# WX0_012_462DL.net
KiCad netlist of a schematic drawn in Altium Designer
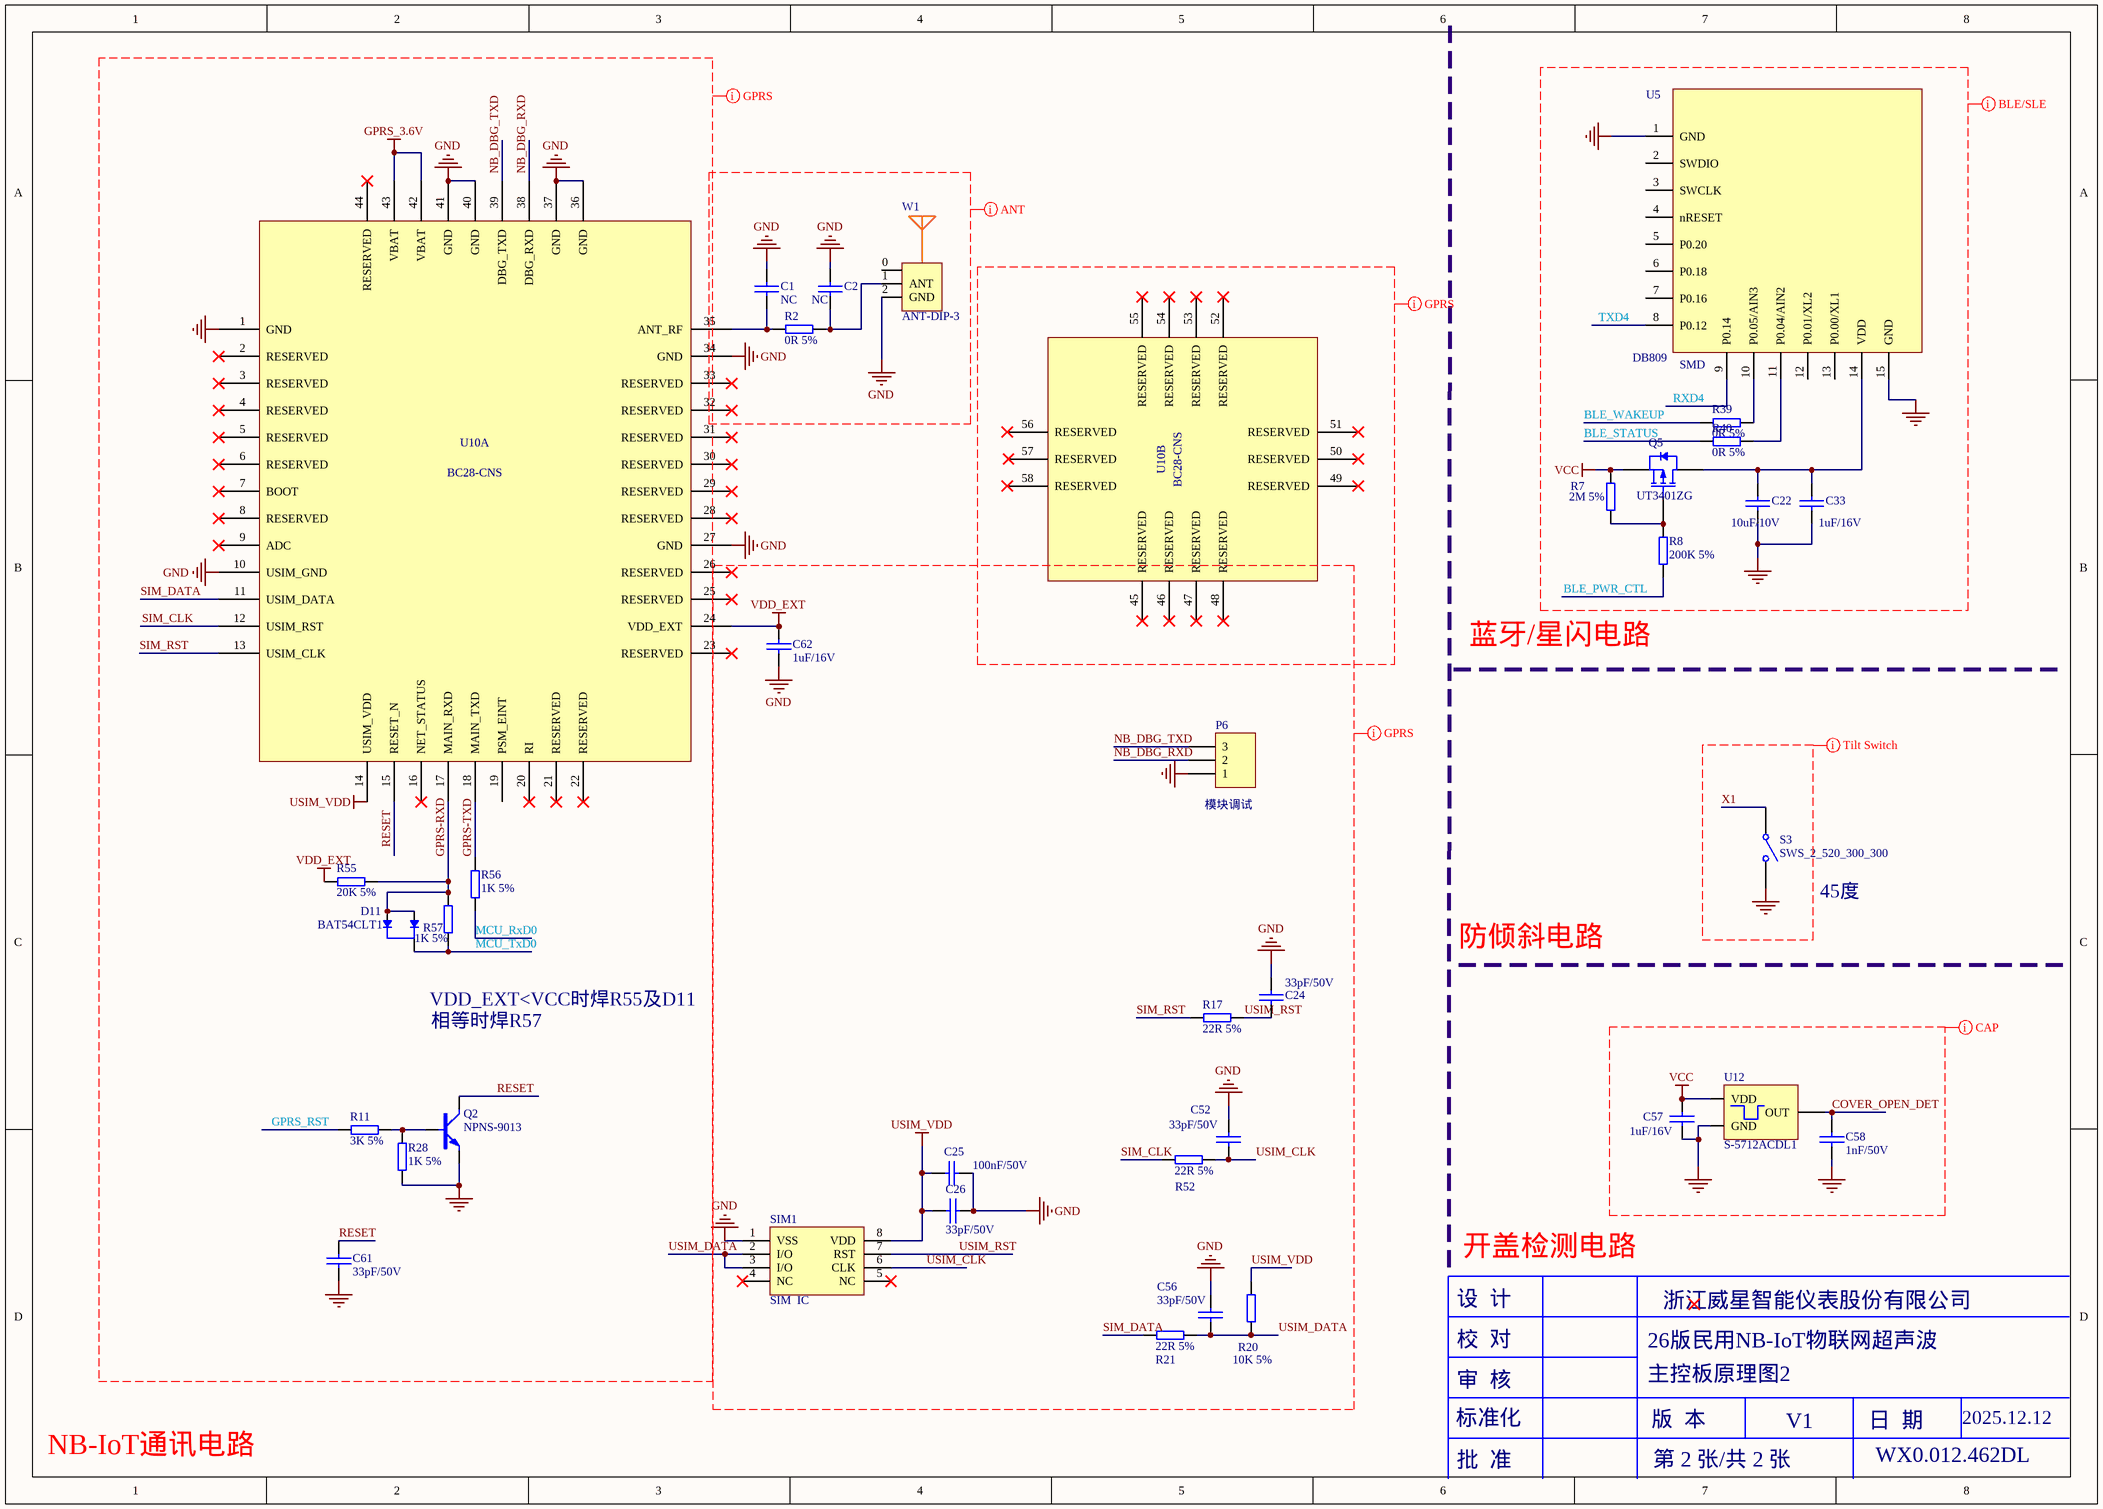
[diagram p0: WX0.012.462DL.SchDoc]

(export (version "E")
  (design (tool "Eeschema 10.0.6"))
  (components
    (comp (ref "C1")
      (value "NC")
      (footprint "CAP0402")
      (libsource (lib "Database_Libs2") (part "CC03JPO9_12P"))
    )
    (comp (ref "C2")
      (value "NC")
      (footprint "CAP0402")
      (libsource (lib "Database_Libs2") (part "CC03JPO9_12P"))
    )
    (comp (ref "C22")
      (value "10uF/10V")
      (footprint "CAP0402")
      (description "106pF,10 V,±10%,0603,村田,GRM188R61A106KE47D")
      (fields (field (name "PART NUMBER") "101020103-0026"))
      (libsource (lib "Database_Libs2") (part "CC03K5R6_10U"))
    )
    (comp (ref "C24")
      (value "33pF/50V")
      (footprint "CAP0402")
      (description "33pF,50 V,±10%,0603,国巨,CC0603KRNPO9BN33")
      (fields (field (name "PART NUMBER") "101020103-0027"))
      (libsource (lib "Database_Libs2") (part "CC03KPO9_33P"))
    )
    (comp (ref "C25")
      (value "100nF/50V")
      (footprint "CAP0402")
      (description "104pF,50 V,±10%,0603,国巨,CC0603KRX7R9BB104")
      (fields (field (name "PART NUMBER") "101020103-0021"))
      (libsource (lib "Database_Libs2") (part "CC03K7R9_100N"))
    )
    (comp (ref "C26")
      (value "33pF/50V")
      (footprint "CAP0402")
      (description "33pF,50 V,±10%,0603,国巨,CC0603KRNPO9BN33")
      (fields (field (name "PART NUMBER") "101020103-0027"))
      (libsource (lib "Database_Libs2") (part "CC03KPO9_33P"))
    )
    (comp (ref "C33")
      (value "1uF/16V")
      (footprint "CAP0402")
      (description "105pF,16 V,±10%,0603,国巨,CC0603KRX7R7BB105")
      (fields (field (name "PART NUMBER") "101020103-0003"))
      (libsource (lib "Database_Libs2") (part "CC03K7R7_1U"))
    )
    (comp (ref "C52")
      (value "33pF/50V")
      (footprint "CAP0402")
      (description "33pF,50 V,±10%,0603,国巨,CC0603KRNPO9BN33")
      (fields (field (name "PART NUMBER") "101020103-0027"))
      (libsource (lib "Database_Libs2") (part "CC03KPO9_33P"))
    )
    (comp (ref "C56")
      (value "33pF/50V")
      (footprint "CAP0402")
      (description "33pF,50 V,±10%,0603,国巨,CC0603KRNPO9BN33")
      (fields (field (name "PART NUMBER") "101020103-0027"))
      (libsource (lib "Database_Libs2") (part "CC03KPO9_33P"))
    )
    (comp (ref "C57")
      (value "1uF/16V")
      (footprint "CAP0402")
      (description "105pF,16 V,±10%,0603,国巨,CC0603KRX7R7BB105")
      (fields (field (name "PART NUMBER") "101020103-0003"))
      (libsource (lib "Database_Libs2") (part "CC03K7R7_1U"))
    )
    (comp (ref "C58")
      (value "1nF/50V")
      (footprint "CAP0402")
      (description "102pF,50 V,±10%,0603,国巨,CC0603KRX7R9BB102")
      (fields (field (name "PART NUMBER") "101020103-0022"))
      (libsource (lib "Database_Libs2") (part "CC03K7R9_1N"))
    )
    (comp (ref "C61")
      (value "33pF/50V")
      (footprint "CAP0402")
      (description "33pF,50 V,±10%,0603,国巨,CC0603KRNPO9BN33")
      (fields (field (name "PART NUMBER") "101020103-0027"))
      (libsource (lib "Database_Libs2") (part "CC03KPO9_33P"))
    )
    (comp (ref "C62")
      (value "1uF/16V")
      (footprint "CAP0402")
      (description "105pF,16 V,±10%,0603,国巨,CC0603KRX7R7BB105")
      (fields (field (name "PART NUMBER") "101020103-0003"))
      (libsource (lib "Database_Libs1") (part "CC03K7R7_1U"))
    )
    (comp (ref "D11")
      (value "BAT54CLT1")
      (footprint "SOT-23")
      (description "BAT54CLT1，SOT23-3,SOT23-3,0.2 A,0.8 V,30 V,安森美,BAT54CLT1")
      (fields (field (name "PART NUMBER") "101040101-0038"))
      (libsource (lib "Database_Libs2") (part "02_BAT54CLT1"))
    )
    (comp (ref "P6")
      (value "模块调试")
      (footprint "PIN254_1*3*WXHJ")
      (description "1*3 ，Φ1.0 ，2.54mm，直脚,无需焊接器件")
      (fields (field (name "PART NUMBER") "AD_WXHJ_PinHeader_04"))
      (libsource (lib "Database_Libs2") (part "PIN254_1*3*WXHJ"))
    )
    (comp (ref "Q2")
      (value "NPNS-9013")
      (footprint "SOT-323-3_L2.0-W1.3-P1.30-LS2.1-BR")
      (description "9013,NPN,SOT-23,长电,S9013")
      (fields (field (name "PART NUMBER") "101040201-0002"))
      (libsource (lib "Database_Libs2") (part "03_NPNS-9013"))
    )
    (comp (ref "Q5")
      (value "UT3401ZG")
      (footprint "SOT-23")
      (description "UT3401ZG,P-MOS,SOT-23,UTC,UT3401ZG")
      (fields (field (name "PART NUMBER") "101040201-0013"))
      (libsource (lib "Database_Libs2") (part "03_P-UT3401ZG"))
    )
    (comp (ref "R2")
      (value "0R 5%")
      (footprint "RES0402")
      (description "国巨,±5%,0603,,155 ℃,-55 ℃,RC0603J2-070RL,无铅,200 ppm/℃,1/10W,,0R")
      (fields (field (name "PART NUMBER") "101010103-0001"))
      (libsource (lib "Database_Libs2") (part "RC03J_0R"))
    )
    (comp (ref "R7")
      (value "2M 5%")
      (footprint "RES0402")
      (description "国巨,±5%,0603,,155 ℃,-55 ℃,RC0603JR-072ML,含铅,100 ppm/℃,1/10W,,2M")
      (fields (field (name "PART NUMBER") "101010103-0025"))
      (libsource (lib "Database_Libs2") (part "RC03J_2M"))
    )
    (comp (ref "R8")
      (value "200K 5%")
      (footprint "RES0402")
      (description "10K±5%,1/10W,0603")
      (fields (field (name "PART NUMBER") "101010103-0003"))
      (libsource (lib "Database_Libs1") (part "RC03JF_10K"))
    )
    (comp (ref "R11")
      (value "3K 5%")
      (footprint "RES0402")
      (description "国巨,±5%,0603,,155 ℃,-55 ℃,RC0603JR-073KL,无铅,100 ppm/℃,1/10W,,3K")
      (fields (field (name "PART NUMBER") "101010103-0006"))
      (libsource (lib "Database_Libs2") (part "RC03J_3K"))
    )
    (comp (ref "R17")
      (value "22R 5%")
      (footprint "RES0402")
      (description "国巨,±5%,0603,,155 ℃,-55 ℃,RC0603JR-0722RL,无铅,200 ppm/℃,1/10W,,22欧")
      (fields (field (name "PART NUMBER") "101010103-0009"))
      (libsource (lib "Database_Libs2") (part "RC03J_22R"))
    )
    (comp (ref "R20")
      (value "10K 5%")
      (footprint "RES0402")
      (description "国巨,±5%,0603,,155 ℃,-55 ℃,RC0603JR-0710KL,无铅,200 ppm/℃,1/10W,,10K")
      (fields (field (name "PART NUMBER") "101010103-0003"))
      (libsource (lib "Database_Libs2") (part "RC03J_10K"))
    )
    (comp (ref "R21")
      (value "22R 5%")
      (footprint "RES0402")
      (description "国巨,±5%,0603,,155 ℃,-55 ℃,RC0603JR-0722RL,无铅,200 ppm/℃,1/10W,,22欧")
      (fields (field (name "PART NUMBER") "101010103-0009"))
      (libsource (lib "Database_Libs2") (part "RC03J_22R"))
    )
    (comp (ref "R28")
      (value "1K 5%")
      (footprint "RES0402")
      (description "1K,±5%,1/10W,0603,国巨,RC0603JR-071KL")
      (fields (field (name "PART NUMBER") "101010103-0008"))
      (libsource (lib "Database_Libs2") (part "RC03J_1K"))
    )
    (comp (ref "R39")
      (value "0R 5%")
      (footprint "RES0402")
      (description "国巨,±5%,0603,,155 ℃,-55 ℃,RC0603J2-070RL,无铅,200 ppm/℃,1/10W,,0R")
      (fields (field (name "PART NUMBER") "101010103-0001"))
      (libsource (lib "Database_Libs2") (part "RC03J_0R"))
    )
    (comp (ref "R40")
      (value "0R 5%")
      (footprint "RES0402")
      (description "国巨,±5%,0603,,155 ℃,-55 ℃,RC0603J2-070RL,无铅,200 ppm/℃,1/10W,,0R")
      (fields (field (name "PART NUMBER") "101010103-0001"))
      (libsource (lib "Database_Libs2") (part "RC03J_0R"))
    )
    (comp (ref "R52")
      (value "22R 5%")
      (footprint "RES0402")
      (description "国巨,±5%,0603,,155 ℃,-55 ℃,RC0603JR-0722RL,无铅,200 ppm/℃,1/10W,,22欧")
      (fields (field (name "PART NUMBER") "101010103-0009"))
      (libsource (lib "Database_Libs2") (part "RC03J_22R"))
    )
    (comp (ref "R55")
      (value "20K 5%")
      (footprint "RES0402")
      (description "国巨,±5%,0603,,155 ℃,-55 ℃,RC0603JR-0720KL,无铅,200 ppm/℃,1/10W,,20K")
      (fields (field (name "PART NUMBER") "101010103-0004"))
      (libsource (lib "Database_Libs2") (part "RC03J_20K"))
    )
    (comp (ref "R56")
      (value "1K 5%")
      (footprint "RES0402")
      (description "220K,±5%,1/10W,0603,国巨,RC0603JR-07220KL")
      (fields (field (name "PART NUMBER") "101010103-0044"))
      (libsource (lib "Database_Libs2") (part "RC03J_220K"))
    )
    (comp (ref "R57")
      (value "1K 5%")
      (footprint "RES0402")
      (description "220K,±5%,1/10W,0603,国巨,RC0603JR-07220KL")
      (fields (field (name "PART NUMBER") "101010103-0044"))
      (libsource (lib "Database_Libs2") (part "RC03J_220K"))
    )
    (comp (ref "S3")
      (value "SWS_2_520_300_300")
      (footprint "SWS_2_520_300")
      (description "CSX-SEN-645B,垂直45°开关转换,3*5.2mm,360°任意方位倾斜检测,深圳市成晟科技有限公司")
      (fields (field (name "PART NUMBER") "1011001-0051"))
      (libsource (lib "Database_Libs2") (part "07_SWS_2_520_300_300"))
    )
    (comp (ref "SIM1")
      (value "SIM  IC")
      (footprint "SIMIC")
      (libsource (lib "PCB_Project") (part "SIMCARD_1"))
    )
    (comp (ref "U5")
      (value "DB809")
      (footprint "DB809")
      (description "北高智蓝牙模块DB809")
      (fields (field (name "PART NUMBER") "1011402-0194") (field (name "SMD/DIP") "SMD"))
      (libsource (lib "Database_Libs2") (part "01_DB809"))
    )
    (comp (ref "U10")
      (value "BC28-CNS")
      (footprint "BC28-CNS")
      (description "BC28-CNS Moudle 58Pin 15.8X17.7mm H2.2mm RO")
      (fields (field (name "MANUFACTURER") "Quectel"))
      (libsource (lib "") (part "BC28-CNS_1"))
    )
    (comp (ref "U12")
      (value "S-5712ACDL1")
      (footprint "SOT-23")
      (description "S-5712ACDL1,SOT23-3,3.5 V,1.6 V,2 uA,精工电子,S-5712ACDL1")
      (fields (field (name "PART NUMBER") "1010504-0002"))
      (libsource (lib "Database_Libs2") (part "01_S-5712ACDL1"))
    )
    (comp (ref "W1")
      (value "ANT-DIP-3")
      (footprint "ANT-DIP-3")
      (libsource (lib "Connect_WX") (part "ANT-DIP-3"))
    )
  )
  (nets
    (net (code "1") (name "/BLE_PWR_CTL") (class "Default")
      (node (ref "R8") (pin "1") (pinfunction "1_1") (pintype "passive"))
    )
    (net (code "2") (name "/BLE_STATUS") (class "Default")
      (node (ref "R40") (pin "2") (pinfunction "2_2") (pintype "passive"))
    )
    (net (code "3") (name "/BLE_WAKEUP") (class "Default")
      (node (ref "R39") (pin "1") (pinfunction "1_1") (pintype "passive"))
    )
    (net (code "4") (name "/COVER_OPEN_DET") (class "Default")
      (node (ref "C58") (pin "1") (pinfunction "1_1") (pintype "passive"))
      (node (ref "U12") (pin "2") (pinfunction "OUT_2") (pintype "passive"))
    )
    (net (code "5") (name "/GPRS-RXD") (class "Default")
      (node (ref "D11") (pin "1") (pinfunction "A_1") (pintype "passive"))
      (node (ref "D11") (pin "2") (pinfunction "A_2") (pintype "passive"))
      (node (ref "R55") (pin "2") (pinfunction "2_2") (pintype "passive"))
      (node (ref "R57") (pin "1") (pinfunction "1_1") (pintype "passive"))
      (node (ref "U10") (pin "17") (pinfunction "MAIN_RXD_17") (pintype "passive"))
    )
    (net (code "6") (name "/GPRS-TXD") (class "Default")
      (node (ref "R56") (pin "2") (pinfunction "2_2") (pintype "passive"))
      (node (ref "U10") (pin "18") (pinfunction "MAIN_TXD_18") (pintype "passive"))
    )
    (net (code "7") (name "/GPRS_RST") (class "Default")
      (node (ref "R11") (pin "1") (pinfunction "1_1") (pintype "passive"))
    )
    (net (code "8") (name "/MCU_RxD0") (class "Default")
      (node (ref "R56") (pin "1") (pinfunction "1_1") (pintype "passive"))
    )
    (net (code "9") (name "/MCU_TxD0") (class "Default")
      (node (ref "D11") (pin "3") (pinfunction "C_3") (pintype "passive"))
      (node (ref "R57") (pin "2") (pinfunction "2_2") (pintype "passive"))
    )
    (net (code "10") (name "/NB_DBG_RXD") (class "Default")
      (node (ref "P6") (pin "2") (pinfunction "2_2") (pintype "passive"))
      (node (ref "U10") (pin "38") (pinfunction "DBG_RXD_38") (pintype "passive"))
    )
    (net (code "11") (name "/NB_DBG_TXD") (class "Default")
      (node (ref "P6") (pin "3") (pinfunction "3_3") (pintype "passive"))
      (node (ref "U10") (pin "39") (pinfunction "DBG_TXD_39") (pintype "passive"))
    )
    (net (code "12") (name "/RESET") (class "Default")
      (node (ref "C61") (pin "1") (pinfunction "1_1") (pintype "passive"))
      (node (ref "Q2") (pin "3") (pinfunction "C_3") (pintype "passive"))
      (node (ref "U10") (pin "15") (pinfunction "RESET_N_15") (pintype "passive"))
    )
    (net (code "13") (name "/RXD4") (class "Default")
      (node (ref "U5") (pin "9") (pinfunction "P0.14_9") (pintype "passive"))
    )
    (net (code "14") (name "/SIM_CLK") (class "Default")
      (node (ref "R52") (pin "1") (pinfunction "1_1") (pintype "passive"))
      (node (ref "U10") (pin "12") (pinfunction "USIM_RST_12") (pintype "passive"))
    )
    (net (code "15") (name "/SIM_DATA") (class "Default")
      (node (ref "R21") (pin "1") (pinfunction "1_1") (pintype "passive"))
      (node (ref "U10") (pin "11") (pinfunction "USIM_DATA_11") (pintype "passive"))
    )
    (net (code "16") (name "/SIM_RST") (class "Default")
      (node (ref "R17") (pin "1") (pinfunction "1_1") (pintype "passive"))
      (node (ref "U10") (pin "13") (pinfunction "USIM_CLK_13") (pintype "passive"))
    )
    (net (code "17") (name "/TXD4") (class "Default")
      (node (ref "U5") (pin "8") (pinfunction "P0.12_8") (pintype "passive"))
    )
    (net (code "18") (name "/USIM_CLK") (class "Default")
      (node (ref "C52") (pin "1") (pinfunction "1_1") (pintype "passive"))
      (node (ref "R52") (pin "2") (pinfunction "2_2") (pintype "passive"))
      (node (ref "SIM1") (pin "6") (pinfunction "CLK_6") (pintype "passive"))
    )
    (net (code "19") (name "/USIM_DATA") (class "Default")
      (node (ref "C56") (pin "1") (pinfunction "1_1") (pintype "passive"))
      (node (ref "R20") (pin "1") (pinfunction "1_1") (pintype "passive"))
      (node (ref "R21") (pin "2") (pinfunction "2_2") (pintype "passive"))
      (node (ref "SIM1") (pin "2") (pinfunction "I/O_2") (pintype "passive"))
      (node (ref "SIM1") (pin "3") (pinfunction "I/O_3") (pintype "passive"))
    )
    (net (code "20") (name "/USIM_RST") (class "Default")
      (node (ref "C24") (pin "1") (pinfunction "1_1") (pintype "passive"))
      (node (ref "R17") (pin "2") (pinfunction "2_2") (pintype "passive"))
      (node (ref "SIM1") (pin "7") (pinfunction "RST_7") (pintype "passive"))
    )
    (net (code "21") (name "/X1") (class "Default") (node (ref "S3") (pin "1") (pintype "passive")))
    (net (code "22") (name "GND") (class "Default")
      (node (ref "C1") (pin "2") (pinfunction "2_2") (pintype "passive"))
      (node (ref "C2") (pin "2") (pinfunction "2_2") (pintype "passive"))
      (node (ref "C22") (pin "2") (pinfunction "2_2") (pintype "passive"))
      (node (ref "C24") (pin "2") (pinfunction "2_2") (pintype "passive"))
      (node (ref "C25") (pin "1") (pinfunction "1_1") (pintype "passive"))
      (node (ref "C26") (pin "2") (pinfunction "2_2") (pintype "passive"))
      (node (ref "C33") (pin "2") (pinfunction "2_2") (pintype "passive"))
      (node (ref "C52") (pin "2") (pinfunction "2_2") (pintype "passive"))
      (node (ref "C56") (pin "2") (pinfunction "2_2") (pintype "passive"))
      (node (ref "C57") (pin "2") (pinfunction "2_2") (pintype "passive"))
      (node (ref "C58") (pin "2") (pinfunction "2_2") (pintype "passive"))
      (node (ref "C61") (pin "2") (pinfunction "2_2") (pintype "passive"))
      (node (ref "C62") (pin "2") (pinfunction "2_2") (pintype "passive"))
      (node (ref "P6") (pin "1") (pinfunction "1_1") (pintype "passive"))
      (node (ref "Q2") (pin "2") (pinfunction "E_2") (pintype "passive"))
      (node (ref "R28") (pin "1") (pinfunction "1_1") (pintype "passive"))
      (node (ref "S3") (pin "2") (pintype "passive"))
      (node (ref "SIM1") (pin "1") (pinfunction "VSS_1") (pintype "passive"))
      (node (ref "U10") (pin "1") (pinfunction "GND_1") (pintype "passive"))
      (node (ref "U10") (pin "10") (pinfunction "USIM_GND_10") (pintype "passive"))
      (node (ref "U10") (pin "27") (pinfunction "GND_27") (pintype "passive"))
      (node (ref "U10") (pin "34") (pinfunction "GND_34") (pintype "passive"))
      (node (ref "U10") (pin "36") (pinfunction "GND_36") (pintype "passive"))
      (node (ref "U10") (pin "37") (pinfunction "GND_37") (pintype "passive"))
      (node (ref "U10") (pin "40") (pinfunction "GND_40") (pintype "passive"))
      (node (ref "U10") (pin "41") (pinfunction "GND_41") (pintype "passive"))
      (node (ref "U12") (pin "3") (pinfunction "GND_3") (pintype "passive"))
      (node (ref "U5") (pin "1") (pinfunction "GND_1") (pintype "passive"))
      (node (ref "U5") (pin "15") (pinfunction "GND_15") (pintype "passive"))
      (node (ref "W1") (pin "2") (pinfunction "GND_2") (pintype "passive"))
    )
    (net (code "23") (name "GPRS_3.6V") (class "Default")
      (node (ref "U10") (pin "42") (pinfunction "VBAT_42") (pintype "passive"))
      (node (ref "U10") (pin "43") (pinfunction "VBAT_43") (pintype "passive"))
    )
    (net (code "24") (name "Net-(Q2-B)") (class "Default")
      (node (ref "Q2") (pin "1") (pinfunction "B_1") (pintype "passive"))
      (node (ref "R11") (pin "2") (pinfunction "2_2") (pintype "passive"))
      (node (ref "R28") (pin "2") (pinfunction "2_2") (pintype "passive"))
    )
    (net (code "25") (name "Net-(Q5-D)") (class "Default")
      (node (ref "C22") (pin "1") (pinfunction "1_1") (pintype "passive"))
      (node (ref "C33") (pin "1") (pinfunction "1_1") (pintype "passive"))
      (node (ref "Q5") (pin "3") (pinfunction "D_3") (pintype "passive"))
      (node (ref "U5") (pin "14") (pinfunction "VDD_14") (pintype "passive"))
    )
    (net (code "26") (name "Net-(Q5-G)") (class "Default")
      (node (ref "Q5") (pin "1") (pinfunction "G_1") (pintype "passive"))
      (node (ref "R7") (pin "1") (pinfunction "1_1") (pintype "passive"))
      (node (ref "R8") (pin "2") (pinfunction "2_2") (pintype "passive"))
    )
    (net (code "27") (name "Net-(U5-P0.04{slash}AIN2)") (class "Default")
      (node (ref "R40") (pin "1") (pinfunction "1_1") (pintype "passive"))
      (node (ref "U5") (pin "11") (pinfunction "P0.04/AIN2_11") (pintype "passive"))
    )
    (net (code "28") (name "Net-(U5-P0.05{slash}AIN3)") (class "Default")
      (node (ref "R39") (pin "2") (pinfunction "2_2") (pintype "passive"))
      (node (ref "U5") (pin "10") (pinfunction "P0.05/AIN3_10") (pintype "passive"))
    )
    (net (code "29") (name "Net-(U10A-ANT_RF)") (class "Default")
      (node (ref "C1") (pin "1") (pinfunction "1_1") (pintype "passive"))
      (node (ref "R2") (pin "2") (pinfunction "2_2") (pintype "passive"))
      (node (ref "U10") (pin "35") (pinfunction "ANT_RF_35") (pintype "passive"))
    )
    (net (code "30") (name "Net-(W1-ANT)") (class "Default")
      (node (ref "C2") (pin "1") (pinfunction "1_1") (pintype "passive"))
      (node (ref "R2") (pin "1") (pinfunction "1_1") (pintype "passive"))
      (node (ref "W1") (pin "1") (pinfunction "ANT_1") (pintype "passive"))
    )
    (net (code "31") (name "USIM_VDD") (class "Default")
      (node (ref "C25") (pin "2") (pinfunction "2_2") (pintype "passive"))
      (node (ref "C26") (pin "1") (pinfunction "1_1") (pintype "passive"))
      (node (ref "R20") (pin "2") (pinfunction "2_2") (pintype "passive"))
      (node (ref "SIM1") (pin "8") (pinfunction "VDD_8") (pintype "passive"))
      (node (ref "U10") (pin "14") (pinfunction "USIM_VDD_14") (pintype "passive"))
    )
    (net (code "32") (name "VCC") (class "Default")
      (node (ref "C57") (pin "1") (pinfunction "1_1") (pintype "passive"))
      (node (ref "Q5") (pin "2") (pinfunction "S_2") (pintype "passive"))
      (node (ref "R7") (pin "2") (pinfunction "2_2") (pintype "passive"))
      (node (ref "U12") (pin "1") (pinfunction "VDD_1") (pintype "passive"))
    )
    (net (code "33") (name "VDD_EXT") (class "Default")
      (node (ref "C62") (pin "1") (pinfunction "1_1") (pintype "passive"))
      (node (ref "R55") (pin "1") (pinfunction "1_1") (pintype "passive"))
      (node (ref "U10") (pin "24") (pinfunction "VDD_EXT_24") (pintype "passive"))
    )
    (net (code "34") (name "unconnected-(SIM1-NC-Pad4)") (class "Default")
      (node (ref "SIM1") (pin "4") (pinfunction "NC_4") (pintype "passive+no_connect"))
    )
    (net (code "35") (name "unconnected-(SIM1-NC-Pad5)") (class "Default")
      (node (ref "SIM1") (pin "5") (pinfunction "NC_5") (pintype "passive+no_connect"))
    )
    (net (code "36") (name "unconnected-(U5-P0.00{slash}XL1-Pad13)") (class "Default")
      (node (ref "U5") (pin "13") (pinfunction "P0.00/XL1_13") (pintype "passive"))
    )
    (net (code "37") (name "unconnected-(U5-P0.01{slash}XL2-Pad12)") (class "Default")
      (node (ref "U5") (pin "12") (pinfunction "P0.01/XL2_12") (pintype "passive"))
    )
    (net (code "38") (name "unconnected-(U5-P0.16-Pad7)") (class "Default")
      (node (ref "U5") (pin "7") (pinfunction "P0.16_7") (pintype "passive"))
    )
    (net (code "39") (name "unconnected-(U5-P0.18-Pad6)") (class "Default")
      (node (ref "U5") (pin "6") (pinfunction "P0.18_6") (pintype "passive"))
    )
    (net (code "40") (name "unconnected-(U5-P0.20-Pad5)") (class "Default")
      (node (ref "U5") (pin "5") (pinfunction "P0.20_5") (pintype "passive"))
    )
    (net (code "41") (name "unconnected-(U5-SWCLK-Pad3)") (class "Default")
      (node (ref "U5") (pin "3") (pinfunction "SWCLK_3") (pintype "passive"))
    )
    (net (code "42") (name "unconnected-(U5-SWDIO-Pad2)") (class "Default")
      (node (ref "U5") (pin "2") (pinfunction "SWDIO_2") (pintype "passive"))
    )
    (net (code "43") (name "unconnected-(U5-nRESET-Pad4)") (class "Default")
      (node (ref "U5") (pin "4") (pinfunction "nRESET_4") (pintype "passive"))
    )
    (net (code "44") (name "unconnected-(U10A-ADC-Pad9)") (class "Default")
      (node (ref "U10") (pin "9") (pinfunction "ADC_9") (pintype "passive+no_connect"))
    )
    (net (code "45") (name "unconnected-(U10A-BOOT-Pad7)") (class "Default")
      (node (ref "U10") (pin "7") (pinfunction "BOOT_7") (pintype "passive+no_connect"))
    )
    (net (code "46") (name "unconnected-(U10A-NET_STATUS-Pad16)") (class "Default")
      (node (ref "U10") (pin "16") (pinfunction "NET_STATUS_16") (pintype "passive+no_connect"))
    )
    (net (code "47") (name "unconnected-(U10A-PSM_EINT-Pad19)") (class "Default")
      (node (ref "U10") (pin "19") (pinfunction "PSM_EINT_19") (pintype "passive"))
    )
    (net (code "48") (name "unconnected-(U10A-RESERVED-Pad2)") (class "Default")
      (node (ref "U10") (pin "2") (pinfunction "RESERVED_2") (pintype "passive+no_connect"))
    )
    (net (code "49") (name "unconnected-(U10A-RESERVED-Pad3)") (class "Default")
      (node (ref "U10") (pin "3") (pinfunction "RESERVED_3") (pintype "passive+no_connect"))
    )
    (net (code "50") (name "unconnected-(U10A-RESERVED-Pad4)") (class "Default")
      (node (ref "U10") (pin "4") (pinfunction "RESERVED_4") (pintype "passive+no_connect"))
    )
    (net (code "51") (name "unconnected-(U10A-RESERVED-Pad5)") (class "Default")
      (node (ref "U10") (pin "5") (pinfunction "RESERVED_5") (pintype "passive+no_connect"))
    )
    (net (code "52") (name "unconnected-(U10A-RESERVED-Pad6)") (class "Default")
      (node (ref "U10") (pin "6") (pinfunction "RESERVED_6") (pintype "passive+no_connect"))
    )
    (net (code "53") (name "unconnected-(U10A-RESERVED-Pad8)") (class "Default")
      (node (ref "U10") (pin "8") (pinfunction "RESERVED_8") (pintype "passive+no_connect"))
    )
    (net (code "54") (name "unconnected-(U10A-RESERVED-Pad21)") (class "Default")
      (node (ref "U10") (pin "21") (pinfunction "RESERVED_21") (pintype "passive+no_connect"))
    )
    (net (code "55") (name "unconnected-(U10A-RESERVED-Pad22)") (class "Default")
      (node (ref "U10") (pin "22") (pinfunction "RESERVED_22") (pintype "passive+no_connect"))
    )
    (net (code "56") (name "unconnected-(U10A-RESERVED-Pad23)") (class "Default")
      (node (ref "U10") (pin "23") (pinfunction "RESERVED_23") (pintype "passive+no_connect"))
    )
    (net (code "57") (name "unconnected-(U10A-RESERVED-Pad25)") (class "Default")
      (node (ref "U10") (pin "25") (pinfunction "RESERVED_25") (pintype "passive+no_connect"))
    )
    (net (code "58") (name "unconnected-(U10A-RESERVED-Pad26)") (class "Default")
      (node (ref "U10") (pin "26") (pinfunction "RESERVED_26") (pintype "passive+no_connect"))
    )
    (net (code "59") (name "unconnected-(U10A-RESERVED-Pad28)") (class "Default")
      (node (ref "U10") (pin "28") (pinfunction "RESERVED_28") (pintype "passive+no_connect"))
    )
    (net (code "60") (name "unconnected-(U10A-RESERVED-Pad29)") (class "Default")
      (node (ref "U10") (pin "29") (pinfunction "RESERVED_29") (pintype "passive+no_connect"))
    )
    (net (code "61") (name "unconnected-(U10A-RESERVED-Pad30)") (class "Default")
      (node (ref "U10") (pin "30") (pinfunction "RESERVED_30") (pintype "passive+no_connect"))
    )
    (net (code "62") (name "unconnected-(U10A-RESERVED-Pad31)") (class "Default")
      (node (ref "U10") (pin "31") (pinfunction "RESERVED_31") (pintype "passive+no_connect"))
    )
    (net (code "63") (name "unconnected-(U10A-RESERVED-Pad32)") (class "Default")
      (node (ref "U10") (pin "32") (pinfunction "RESERVED_32") (pintype "passive+no_connect"))
    )
    (net (code "64") (name "unconnected-(U10A-RESERVED-Pad33)") (class "Default")
      (node (ref "U10") (pin "33") (pinfunction "RESERVED_33") (pintype "passive+no_connect"))
    )
    (net (code "65") (name "unconnected-(U10A-RESERVED-Pad44)") (class "Default")
      (node (ref "U10") (pin "44") (pinfunction "RESERVED_44") (pintype "passive+no_connect"))
    )
    (net (code "66") (name "unconnected-(U10A-RI-Pad20)") (class "Default")
      (node (ref "U10") (pin "20") (pinfunction "RI_20") (pintype "passive+no_connect"))
    )
    (net (code "67") (name "unconnected-(U10B-RESERVED-Pad45)") (class "Default")
      (node (ref "U10") (pin "45") (pinfunction "RESERVED_45") (pintype "passive+no_connect"))
    )
    (net (code "68") (name "unconnected-(U10B-RESERVED-Pad46)") (class "Default")
      (node (ref "U10") (pin "46") (pinfunction "RESERVED_46") (pintype "passive+no_connect"))
    )
    (net (code "69") (name "unconnected-(U10B-RESERVED-Pad47)") (class "Default")
      (node (ref "U10") (pin "47") (pinfunction "RESERVED_47") (pintype "passive+no_connect"))
    )
    (net (code "70") (name "unconnected-(U10B-RESERVED-Pad48)") (class "Default")
      (node (ref "U10") (pin "48") (pinfunction "RESERVED_48") (pintype "passive+no_connect"))
    )
    (net (code "71") (name "unconnected-(U10B-RESERVED-Pad49)") (class "Default")
      (node (ref "U10") (pin "49") (pinfunction "RESERVED_49") (pintype "passive+no_connect"))
    )
    (net (code "72") (name "unconnected-(U10B-RESERVED-Pad50)") (class "Default")
      (node (ref "U10") (pin "50") (pinfunction "RESERVED_50") (pintype "passive+no_connect"))
    )
    (net (code "73") (name "unconnected-(U10B-RESERVED-Pad51)") (class "Default")
      (node (ref "U10") (pin "51") (pinfunction "RESERVED_51") (pintype "passive+no_connect"))
    )
    (net (code "74") (name "unconnected-(U10B-RESERVED-Pad52)") (class "Default")
      (node (ref "U10") (pin "52") (pinfunction "RESERVED_52") (pintype "passive+no_connect"))
    )
    (net (code "75") (name "unconnected-(U10B-RESERVED-Pad53)") (class "Default")
      (node (ref "U10") (pin "53") (pinfunction "RESERVED_53") (pintype "passive+no_connect"))
    )
    (net (code "76") (name "unconnected-(U10B-RESERVED-Pad54)") (class "Default")
      (node (ref "U10") (pin "54") (pinfunction "RESERVED_54") (pintype "passive+no_connect"))
    )
    (net (code "77") (name "unconnected-(U10B-RESERVED-Pad55)") (class "Default")
      (node (ref "U10") (pin "55") (pinfunction "RESERVED_55") (pintype "passive+no_connect"))
    )
    (net (code "78") (name "unconnected-(U10B-RESERVED-Pad56)") (class "Default")
      (node (ref "U10") (pin "56") (pinfunction "RESERVED_56") (pintype "passive+no_connect"))
    )
    (net (code "79") (name "unconnected-(U10B-RESERVED-Pad57)") (class "Default")
      (node (ref "U10") (pin "57") (pinfunction "RESERVED_57") (pintype "passive"))
    )
    (net (code "80") (name "unconnected-(U10B-RESERVED-Pad58)") (class "Default")
      (node (ref "U10") (pin "58") (pinfunction "RESERVED_58") (pintype "passive+no_connect"))
    )
    (net (code "81") (name "unconnected-(W1-NC-Pad0)") (class "Default")
      (node (ref "W1") (pin "0") (pinfunction "NC_0") (pintype "passive"))
    )
  )
)
